# daughtercard.net
KiCad netlist of a schematic drawn in EAGLE
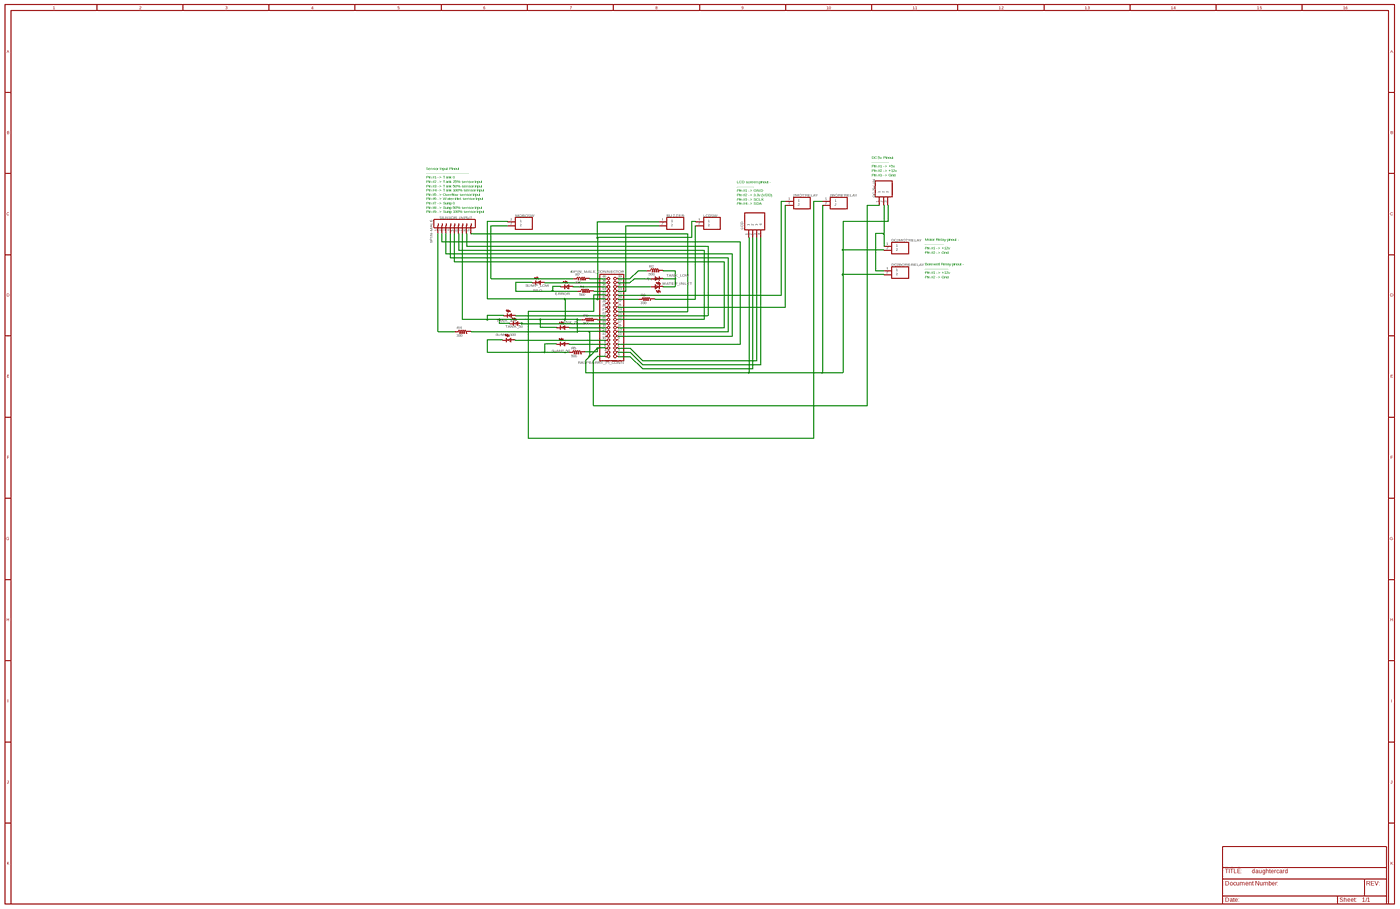
[diagram p0: schematic, sheet 1, overview]
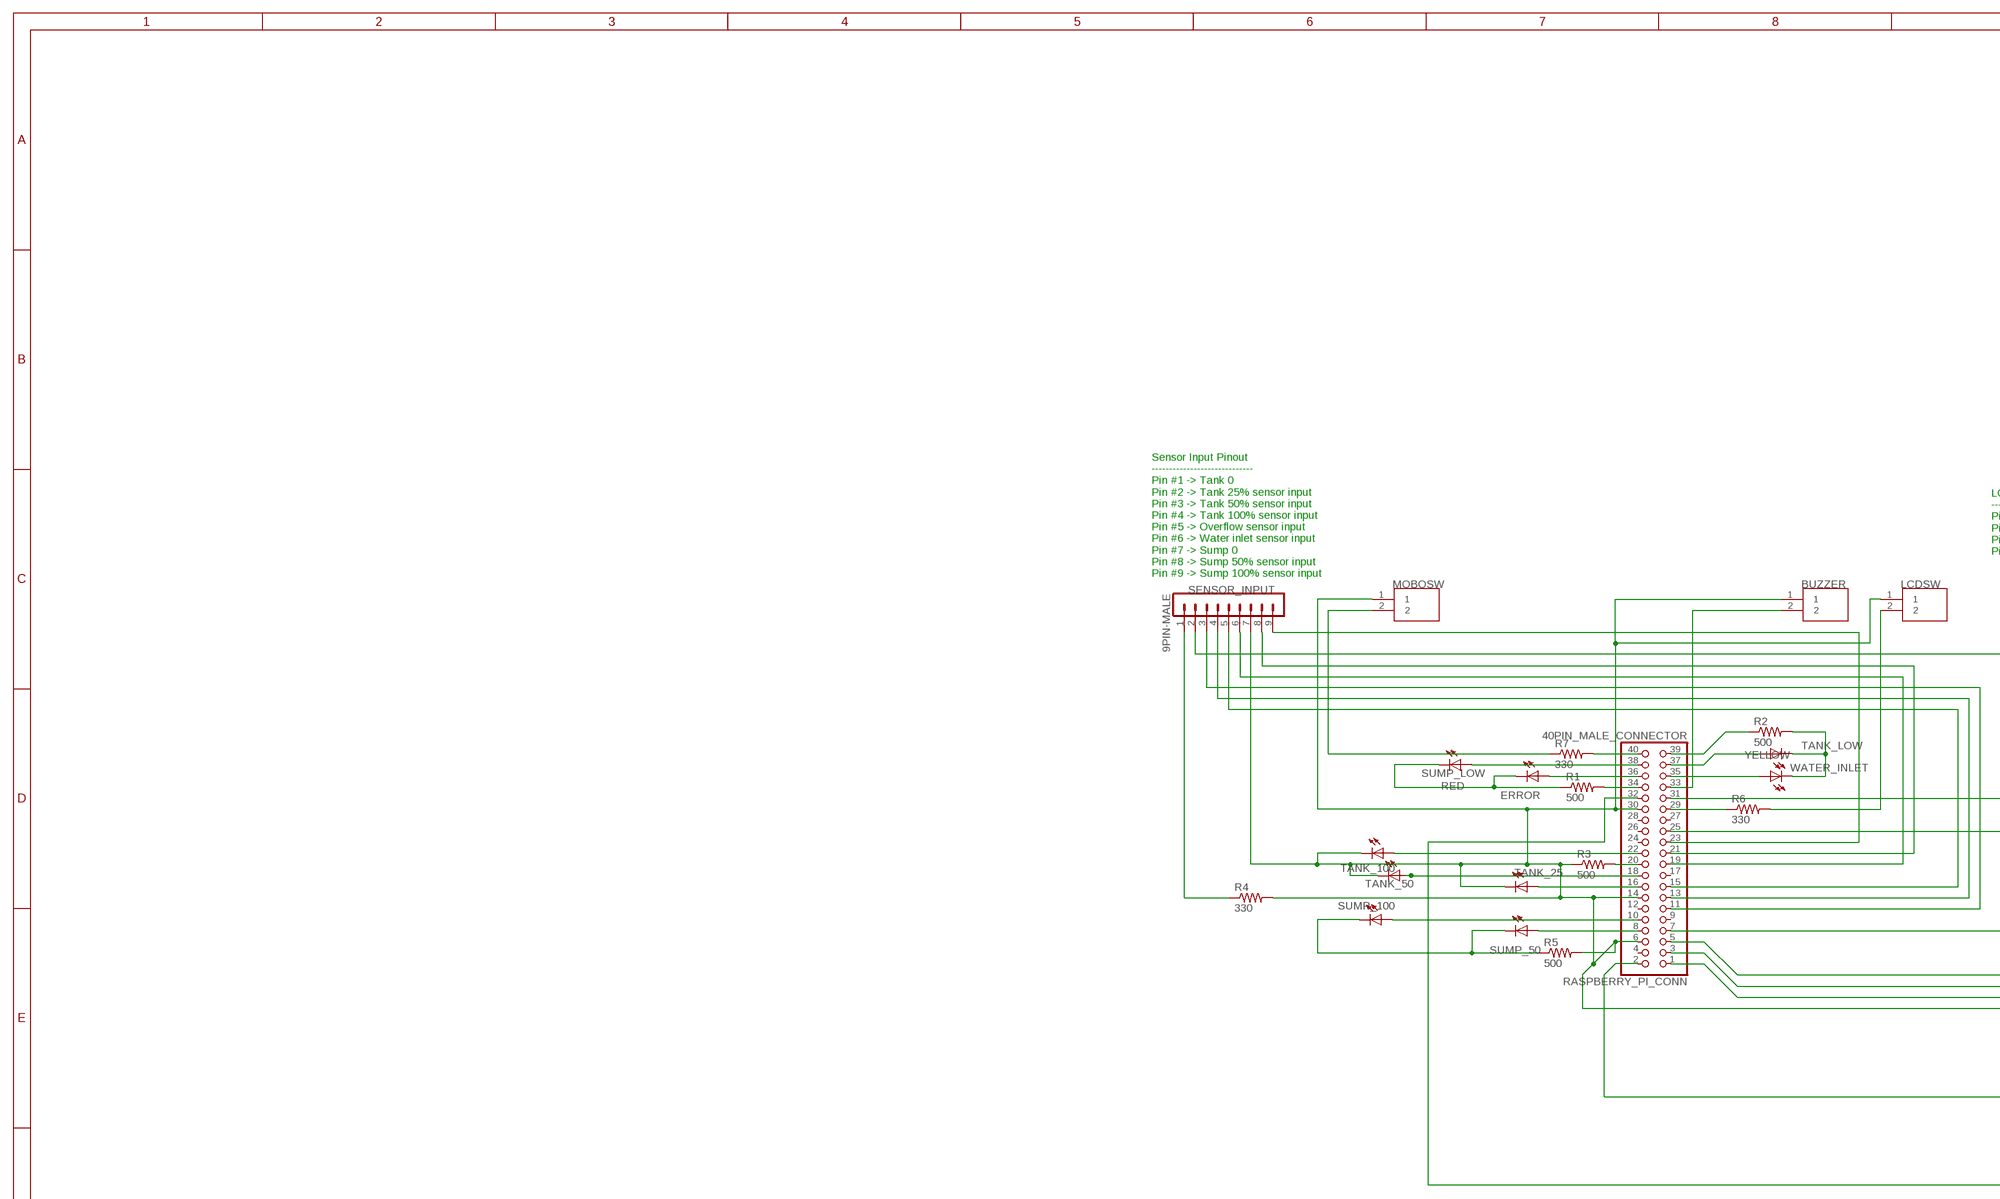
[diagram p1: schematic, sheet 1, part 1 of 4]
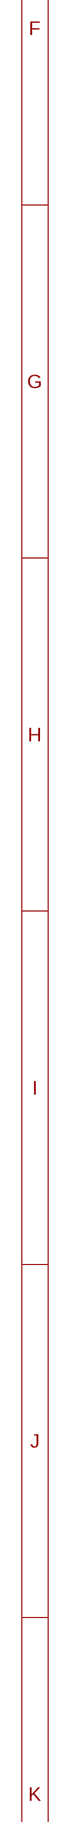
[diagram p2: schematic, sheet 1, part 2 of 4]
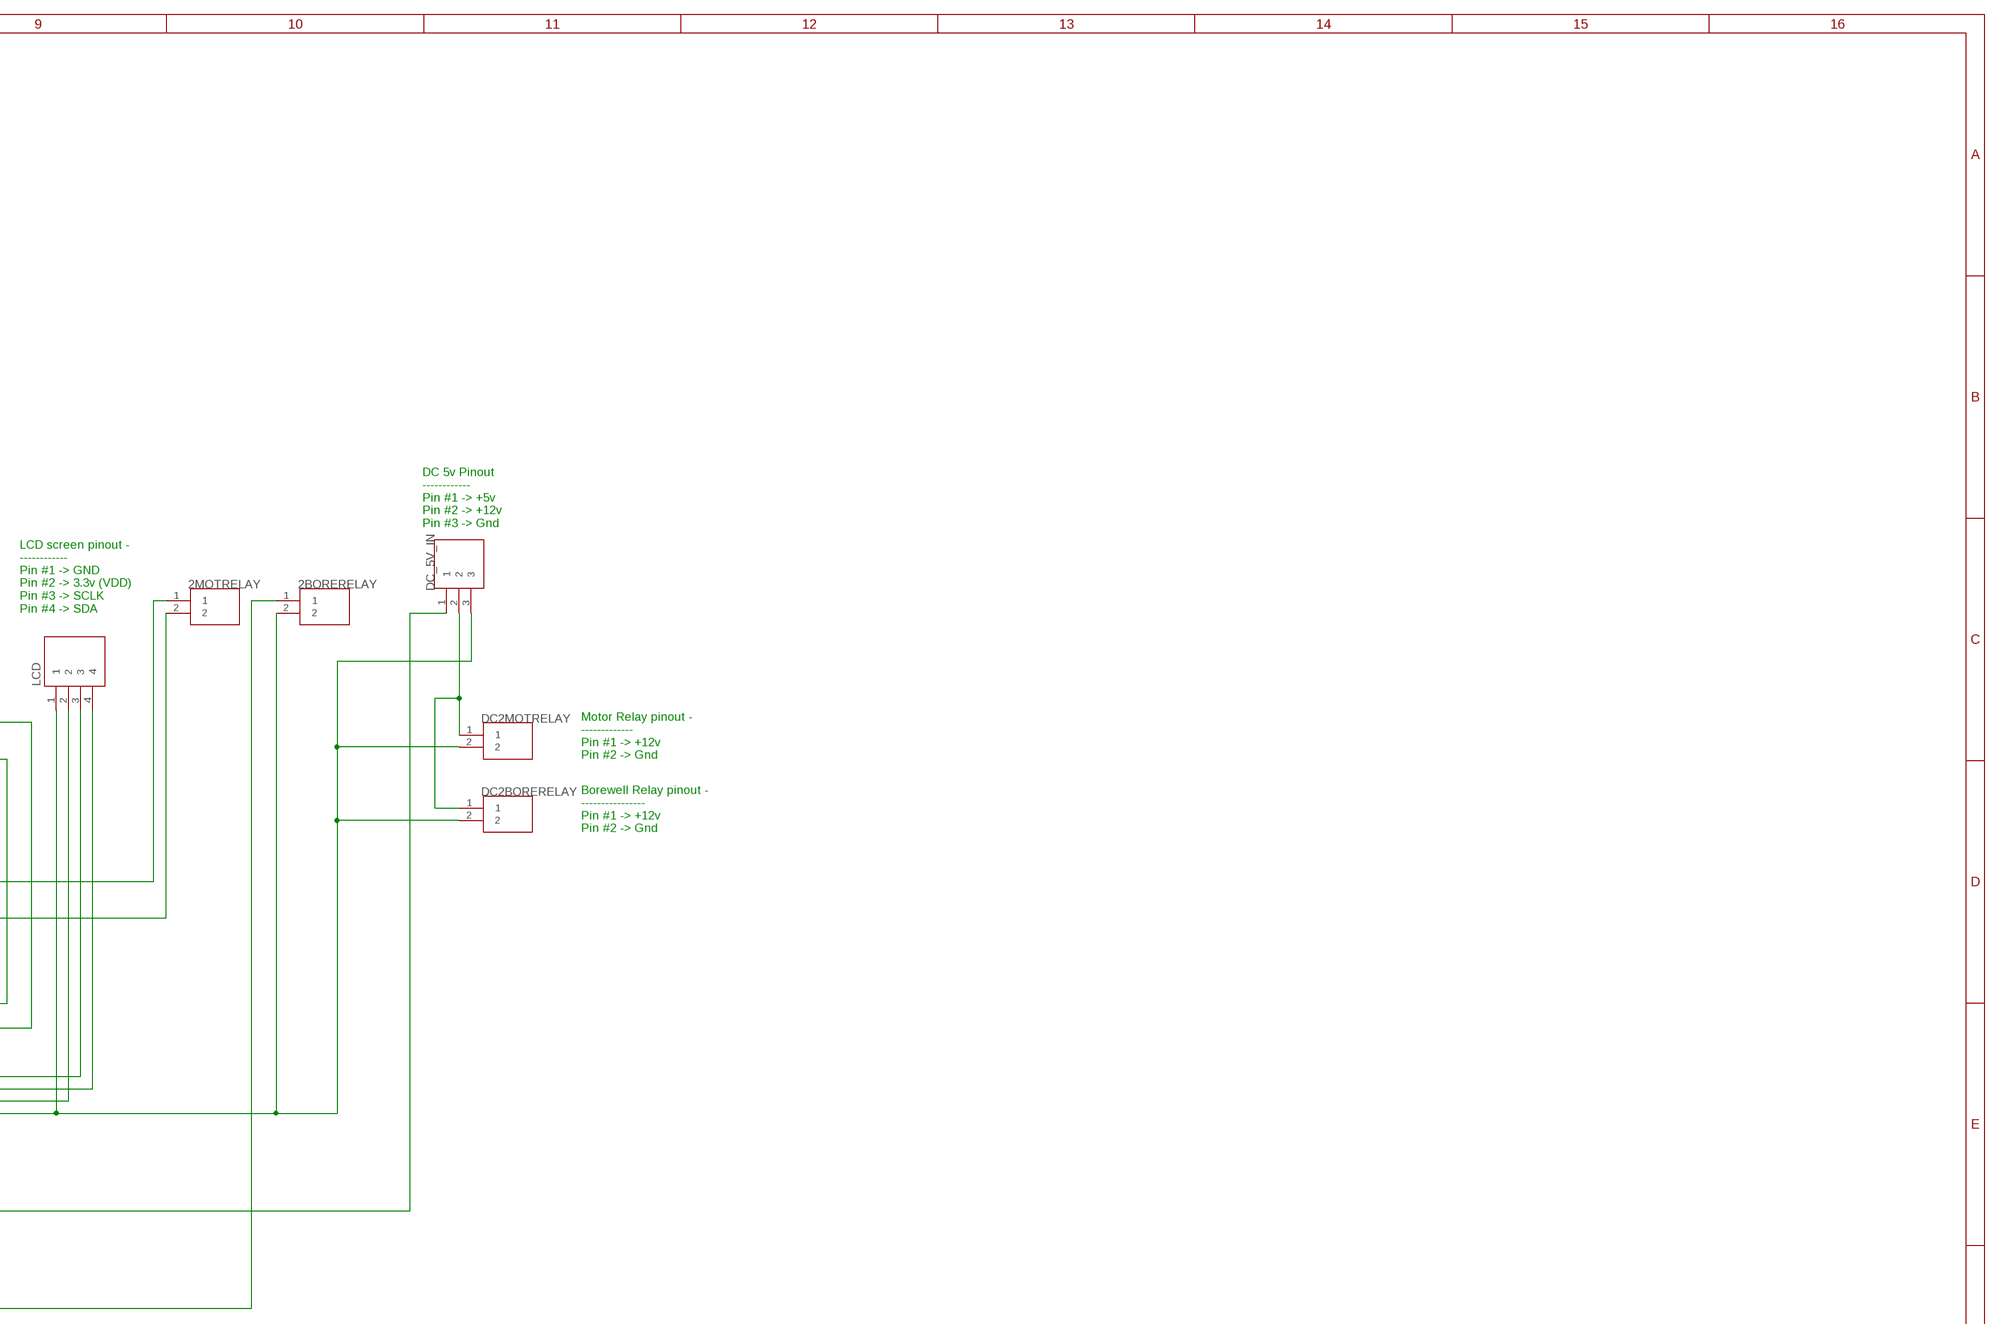
[diagram p3: schematic, sheet 1, part 3 of 4]
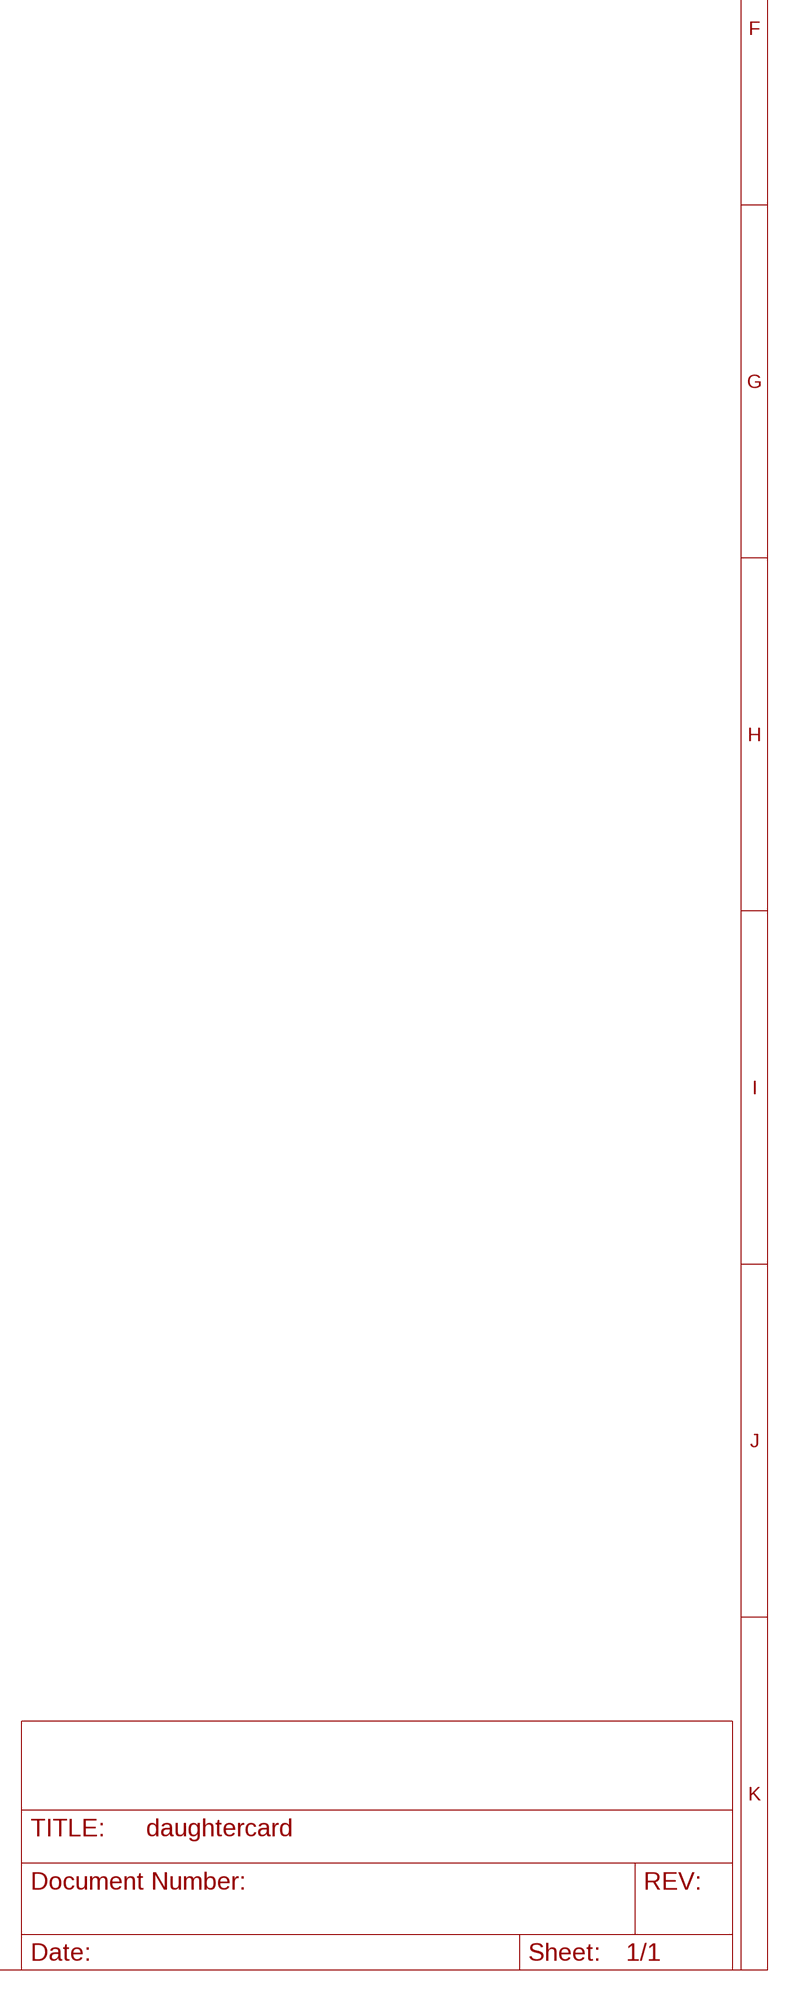
[diagram p4: schematic, sheet 1, part 4 of 4]

(export (version "E")
  (design (tool "Eeschema 10.0.6"))
  (components
    (comp (ref "2BORERELAY")
      (value "440055-2")
      (footprint "eagle-import:TE_440055-2")
      (fields (field (name "MF") "TE Connectivity"))
      (libsource (lib "eagle-import") (part "440055-2"))
    )
    (comp (ref "2MOTRELAY")
      (value "440055-2")
      (footprint "eagle-import:TE_440055-2")
      (fields (field (name "MF") "TE Connectivity"))
      (libsource (lib "eagle-import") (part "440055-2"))
    )
    (comp (ref "BUZZER")
      (value "440055-2")
      (footprint "eagle-import:TE_440055-2")
      (fields (field (name "MF") "TE Connectivity"))
      (libsource (lib "eagle-import") (part "440055-2"))
    )
    (comp (ref "DC2BORERELAY")
      (value "440055-2")
      (footprint "eagle-import:TE_440055-2")
      (fields (field (name "MF") "TE Connectivity"))
      (libsource (lib "eagle-import") (part "440055-2"))
    )
    (comp (ref "DC2MOTRELAY")
      (value "440055-2")
      (footprint "eagle-import:TE_440055-2")
      (fields (field (name "MF") "TE Connectivity"))
      (libsource (lib "eagle-import") (part "440055-2"))
    )
    (comp (ref "DC_5V_IN")
      (value "440052-3")
      (footprint "eagle-import:TE_440052-3")
      (fields (field (name "MF") "TE Connectivity"))
      (libsource (lib "eagle-import") (part "440052-3"))
    )
    (comp (ref "ERROR")
      (value "RED")
      (footprint "eagle-import:LED3MM")
      (libsource (lib "eagle-import") (part "LED3MM"))
    )
    (comp (ref "LCD")
      (value "110990030")
      (footprint "eagle-import:SEEED_110990030")
      (fields (field (name "MF") "Seeed Technology Co., Ltd"))
      (libsource (lib "eagle-import") (part "110990030"))
    )
    (comp (ref "LCDSW")
      (value "440055-2")
      (footprint "eagle-import:TE_440055-2")
      (fields (field (name "MF") "TE Connectivity"))
      (libsource (lib "eagle-import") (part "440055-2"))
    )
    (comp (ref "MOBOSW")
      (value "440055-2")
      (footprint "eagle-import:TE_440055-2")
      (fields (field (name "MF") "TE Connectivity"))
      (libsource (lib "eagle-import") (part "440055-2"))
    )
    (comp (ref "R1")
      (value "500")
      (footprint "eagle-import:0204V")
      (libsource (lib "eagle-import") (part "R-US_0204/2V"))
    )
    (comp (ref "R2")
      (value "500")
      (footprint "eagle-import:0204V")
      (libsource (lib "eagle-import") (part "R-US_0204/2V"))
    )
    (comp (ref "R3")
      (value "500")
      (footprint "eagle-import:0204_7")
      (libsource (lib "eagle-import") (part "R-US_0204/7"))
    )
    (comp (ref "R4")
      (value "330")
      (footprint "eagle-import:0204_7")
      (libsource (lib "eagle-import") (part "R-US_0204/7"))
    )
    (comp (ref "R5")
      (value "500")
      (footprint "eagle-import:0204V")
      (libsource (lib "eagle-import") (part "R-US_0204/2V"))
    )
    (comp (ref "R6")
      (value "330")
      (footprint "eagle-import:0204V")
      (libsource (lib "eagle-import") (part "R-US_0204/2V"))
    )
    (comp (ref "R7")
      (value "330")
      (footprint "eagle-import:0204V")
      (libsource (lib "eagle-import") (part "R-US_0204/2V"))
    )
    (comp (ref "RASPBERRY_PI_CONN")
      (value "40PIN_MALE_CONNECTOR")
      (footprint "eagle-import:2X20")
      (libsource (lib "eagle-import") (part "PINHD-2X20"))
    )
    (comp (ref "SENSOR_INPUT")
      (value "9PIN-MALE")
      (footprint "eagle-import:MA09-1")
      (libsource (lib "eagle-import") (part "MA09-1"))
    )
    (comp (ref "SUMP_50")
      (value "GREEN")
      (footprint "eagle-import:LED3MM")
      (libsource (lib "eagle-import") (part "LED3MM"))
    )
    (comp (ref "SUMP_100")
      (value "GREEN")
      (footprint "eagle-import:LED3MM")
      (libsource (lib "eagle-import") (part "LED3MM"))
    )
    (comp (ref "SUMP_LOW")
      (value "RED")
      (footprint "eagle-import:LED3MM")
      (libsource (lib "eagle-import") (part "LED3MM"))
    )
    (comp (ref "TANK_25")
      (value "GREEN")
      (footprint "eagle-import:LED3MM")
      (libsource (lib "eagle-import") (part "LED3MM"))
    )
    (comp (ref "TANK_50")
      (value "GREEN")
      (footprint "eagle-import:LED3MM")
      (libsource (lib "eagle-import") (part "LED3MM"))
    )
    (comp (ref "TANK_100")
      (value "GREEN")
      (footprint "eagle-import:LED3MM")
      (libsource (lib "eagle-import") (part "LED3MM"))
    )
    (comp (ref "TANK_LOW")
      (value "RED")
      (footprint "eagle-import:LED3MM")
      (libsource (lib "eagle-import") (part "LED3MM"))
    )
    (comp (ref "WATER_INLET")
      (value "YELLOW")
      (footprint "eagle-import:LED3MM")
      (libsource (lib "eagle-import") (part "LED3MM"))
    )
  )
  (nets
    (net (code "1") (name "Net-(2BORERELAY-Pad1)") (class "Default")
      (node (ref "2BORERELAY") (pin "1") (pinfunction "1_1") (pintype "passive"))
      (node (ref "RASPBERRY_PI_CONN") (pin "32") (pinfunction "32_32") (pintype "passive"))
    )
    (net (code "2") (name "Net-(2MOTRELAY-Pad1)") (class "Default")
      (node (ref "2MOTRELAY") (pin "1") (pinfunction "1_1") (pintype "passive"))
      (node (ref "RASPBERRY_PI_CONN") (pin "31") (pinfunction "31_31") (pintype "passive"))
    )
    (net (code "3") (name "Net-(2MOTRELAY-Pad2)") (class "Default")
      (node (ref "2MOTRELAY") (pin "2") (pinfunction "2_2") (pintype "passive"))
      (node (ref "RASPBERRY_PI_CONN") (pin "25") (pinfunction "25_25") (pintype "passive"))
    )
    (net (code "4") (name "Net-(BUZZER-Pad2)") (class "Default")
      (node (ref "BUZZER") (pin "2") (pinfunction "2_2") (pintype "passive"))
      (node (ref "RASPBERRY_PI_CONN") (pin "33") (pinfunction "33_33") (pintype "passive"))
    )
    (net (code "5") (name "Net-(DC2BORERELAY-Pad1)") (class "Default")
      (node (ref "DC2BORERELAY") (pin "1") (pinfunction "1_1") (pintype "passive"))
      (node (ref "DC2MOTRELAY") (pin "1") (pinfunction "1_1") (pintype "passive"))
      (node (ref "DC_5V_IN") (pin "2") (pinfunction "2_2") (pintype "passive"))
    )
    (net (code "6") (name "Net-(DC_5V_IN-Pad1)") (class "Default")
      (node (ref "DC_5V_IN") (pin "1") (pinfunction "1_1") (pintype "passive"))
      (node (ref "RASPBERRY_PI_CONN") (pin "2") (pinfunction "2_2") (pintype "passive"))
    )
    (net (code "7") (name "Net-(ERROR-C)") (class "Default")
      (node (ref "ERROR") (pin "K") (pinfunction "C_K") (pintype "passive"))
      (node (ref "R1") (pin "1") (pinfunction "1_1") (pintype "passive"))
      (node (ref "SUMP_LOW") (pin "K") (pinfunction "C_K") (pintype "passive"))
    )
    (net (code "8") (name "Net-(ERROR-PadA)") (class "Default")
      (node (ref "ERROR") (pin "A") (pinfunction "A_A") (pintype "passive"))
      (node (ref "RASPBERRY_PI_CONN") (pin "36") (pinfunction "36_36") (pintype "passive"))
    )
    (net (code "9") (name "Net-(LCD-Pad2)") (class "Default")
      (node (ref "LCD") (pin "2") (pinfunction "2_2") (pintype "passive"))
      (node (ref "RASPBERRY_PI_CONN") (pin "1") (pinfunction "1_1") (pintype "passive"))
    )
    (net (code "10") (name "Net-(LCD-Pad3)") (class "Default")
      (node (ref "LCD") (pin "3") (pinfunction "3_3") (pintype "passive"))
      (node (ref "RASPBERRY_PI_CONN") (pin "5") (pinfunction "5_5") (pintype "passive"))
    )
    (net (code "11") (name "Net-(LCD-Pad4)") (class "Default")
      (node (ref "LCD") (pin "4") (pinfunction "4_4") (pintype "passive"))
      (node (ref "RASPBERRY_PI_CONN") (pin "3") (pinfunction "3_3") (pintype "passive"))
    )
    (net (code "12") (name "Net-(LCDSW-Pad2)") (class "Default")
      (node (ref "LCDSW") (pin "2") (pinfunction "2_2") (pintype "passive"))
      (node (ref "R6") (pin "2") (pinfunction "2_2") (pintype "passive"))
    )
    (net (code "13") (name "Net-(MOBOSW-Pad2)") (class "Default")
      (node (ref "MOBOSW") (pin "2") (pinfunction "2_2") (pintype "passive"))
      (node (ref "R7") (pin "1") (pinfunction "1_1") (pintype "passive"))
    )
    (net (code "14") (name "Net-(R1-Pad2)") (class "Default")
      (node (ref "R1") (pin "2") (pinfunction "2_2") (pintype "passive"))
      (node (ref "RASPBERRY_PI_CONN") (pin "34") (pinfunction "34_34") (pintype "passive"))
    )
    (net (code "15") (name "Net-(R2-Pad1)") (class "Default")
      (node (ref "R2") (pin "1") (pinfunction "1_1") (pintype "passive"))
      (node (ref "RASPBERRY_PI_CONN") (pin "39") (pinfunction "39_39") (pintype "passive"))
    )
    (net (code "16") (name "Net-(R3-Pad2)") (class "Default")
      (node (ref "R3") (pin "2") (pinfunction "2_2") (pintype "passive"))
      (node (ref "RASPBERRY_PI_CONN") (pin "20") (pinfunction "20_20") (pintype "passive"))
    )
    (net (code "17") (name "Net-(R4-Pad1)") (class "Default")
      (node (ref "R4") (pin "1") (pinfunction "1_1") (pintype "passive"))
      (node (ref "SENSOR_INPUT") (pin "1") (pinfunction "1_1") (pintype "passive"))
    )
    (net (code "18") (name "Net-(R6-Pad1)") (class "Default")
      (node (ref "R6") (pin "1") (pinfunction "1_1") (pintype "passive"))
      (node (ref "RASPBERRY_PI_CONN") (pin "29") (pinfunction "29_29") (pintype "passive"))
    )
    (net (code "19") (name "Net-(R7-Pad2)") (class "Default")
      (node (ref "R7") (pin "2") (pinfunction "2_2") (pintype "passive"))
      (node (ref "RASPBERRY_PI_CONN") (pin "40") (pinfunction "40_40") (pintype "passive"))
    )
    (net (code "20") (name "Net-(RASPBERRY_PI_CONN-Pad7)") (class "Default")
      (node (ref "RASPBERRY_PI_CONN") (pin "7") (pinfunction "7_7") (pintype "passive"))
      (node (ref "SENSOR_INPUT") (pin "2") (pinfunction "2_2") (pintype "passive"))
    )
    (net (code "21") (name "Net-(RASPBERRY_PI_CONN-Pad8)") (class "Default")
      (node (ref "RASPBERRY_PI_CONN") (pin "8") (pinfunction "8_8") (pintype "passive"))
      (node (ref "SUMP_50") (pin "A") (pinfunction "A_A") (pintype "passive"))
    )
    (net (code "22") (name "Net-(RASPBERRY_PI_CONN-Pad10)") (class "Default")
      (node (ref "RASPBERRY_PI_CONN") (pin "10") (pinfunction "10_10") (pintype "passive"))
      (node (ref "SUMP_100") (pin "A") (pinfunction "A_A") (pintype "passive"))
    )
    (net (code "23") (name "Net-(RASPBERRY_PI_CONN-Pad11)") (class "Default")
      (node (ref "RASPBERRY_PI_CONN") (pin "11") (pinfunction "11_11") (pintype "passive"))
      (node (ref "SENSOR_INPUT") (pin "3") (pinfunction "3_3") (pintype "passive"))
    )
    (net (code "24") (name "Net-(RASPBERRY_PI_CONN-Pad13)") (class "Default")
      (node (ref "RASPBERRY_PI_CONN") (pin "13") (pinfunction "13_13") (pintype "passive"))
      (node (ref "SENSOR_INPUT") (pin "4") (pinfunction "4_4") (pintype "passive"))
    )
    (net (code "25") (name "Net-(RASPBERRY_PI_CONN-Pad15)") (class "Default")
      (node (ref "RASPBERRY_PI_CONN") (pin "15") (pinfunction "15_15") (pintype "passive"))
      (node (ref "SENSOR_INPUT") (pin "5") (pinfunction "5_5") (pintype "passive"))
    )
    (net (code "26") (name "Net-(RASPBERRY_PI_CONN-Pad16)") (class "Default")
      (node (ref "RASPBERRY_PI_CONN") (pin "16") (pinfunction "16_16") (pintype "passive"))
      (node (ref "TANK_25") (pin "A") (pinfunction "A_A") (pintype "passive"))
    )
    (net (code "27") (name "Net-(RASPBERRY_PI_CONN-Pad18)") (class "Default")
      (node (ref "RASPBERRY_PI_CONN") (pin "18") (pinfunction "18_18") (pintype "passive"))
      (node (ref "TANK_50") (pin "A") (pinfunction "A_A") (pintype "passive"))
    )
    (net (code "28") (name "Net-(RASPBERRY_PI_CONN-Pad19)") (class "Default")
      (node (ref "RASPBERRY_PI_CONN") (pin "19") (pinfunction "19_19") (pintype "passive"))
      (node (ref "SENSOR_INPUT") (pin "6") (pinfunction "6_6") (pintype "passive"))
    )
    (net (code "29") (name "Net-(RASPBERRY_PI_CONN-Pad21)") (class "Default")
      (node (ref "RASPBERRY_PI_CONN") (pin "21") (pinfunction "21_21") (pintype "passive"))
      (node (ref "SENSOR_INPUT") (pin "8") (pinfunction "8_8") (pintype "passive"))
    )
    (net (code "30") (name "Net-(RASPBERRY_PI_CONN-Pad22)") (class "Default")
      (node (ref "RASPBERRY_PI_CONN") (pin "22") (pinfunction "22_22") (pintype "passive"))
      (node (ref "TANK_100") (pin "A") (pinfunction "A_A") (pintype "passive"))
    )
    (net (code "31") (name "Net-(RASPBERRY_PI_CONN-Pad23)") (class "Default")
      (node (ref "RASPBERRY_PI_CONN") (pin "23") (pinfunction "23_23") (pintype "passive"))
      (node (ref "SENSOR_INPUT") (pin "9") (pinfunction "9_9") (pintype "passive"))
    )
    (net (code "32") (name "Net-(RASPBERRY_PI_CONN-Pad35)") (class "Default")
      (node (ref "RASPBERRY_PI_CONN") (pin "35") (pinfunction "35_35") (pintype "passive"))
      (node (ref "WATER_INLET") (pin "A") (pinfunction "A_A") (pintype "passive"))
    )
    (net (code "33") (name "Net-(RASPBERRY_PI_CONN-Pad37)") (class "Default")
      (node (ref "RASPBERRY_PI_CONN") (pin "37") (pinfunction "37_37") (pintype "passive"))
      (node (ref "TANK_LOW") (pin "A") (pinfunction "A_A") (pintype "passive"))
    )
    (net (code "34") (name "Net-(RASPBERRY_PI_CONN-Pad38)") (class "Default")
      (node (ref "RASPBERRY_PI_CONN") (pin "38") (pinfunction "38_38") (pintype "passive"))
      (node (ref "SUMP_LOW") (pin "A") (pinfunction "A_A") (pintype "passive"))
    )
    (net (code "35") (name "Net-(SUMP_100-C)") (class "Default")
      (node (ref "R5") (pin "1") (pinfunction "1_1") (pintype "passive"))
      (node (ref "SUMP_100") (pin "K") (pinfunction "C_K") (pintype "passive"))
      (node (ref "SUMP_50") (pin "K") (pinfunction "C_K") (pintype "passive"))
    )
    (net (code "36") (name "Net-(TANK_100-C)") (class "Default")
      (node (ref "2BORERELAY") (pin "2") (pinfunction "2_2") (pintype "passive"))
      (node (ref "BUZZER") (pin "1") (pinfunction "1_1") (pintype "passive"))
      (node (ref "DC2BORERELAY") (pin "2") (pinfunction "2_2") (pintype "passive"))
      (node (ref "DC2MOTRELAY") (pin "2") (pinfunction "2_2") (pintype "passive"))
      (node (ref "DC_5V_IN") (pin "3") (pinfunction "3_3") (pintype "passive"))
      (node (ref "LCD") (pin "1") (pinfunction "1_1") (pintype "passive"))
      (node (ref "LCDSW") (pin "1") (pinfunction "1_1") (pintype "passive"))
      (node (ref "MOBOSW") (pin "1") (pinfunction "1_1") (pintype "passive"))
      (node (ref "R3") (pin "1") (pinfunction "1_1") (pintype "passive"))
      (node (ref "R4") (pin "2") (pinfunction "2_2") (pintype "passive"))
      (node (ref "R5") (pin "2") (pinfunction "2_2") (pintype "passive"))
      (node (ref "RASPBERRY_PI_CONN") (pin "14") (pinfunction "14_14") (pintype "passive"))
      (node (ref "RASPBERRY_PI_CONN") (pin "30") (pinfunction "30_30") (pintype "passive"))
      (node (ref "RASPBERRY_PI_CONN") (pin "6") (pinfunction "6_6") (pintype "passive"))
      (node (ref "SENSOR_INPUT") (pin "7") (pinfunction "7_7") (pintype "passive"))
      (node (ref "TANK_100") (pin "K") (pinfunction "C_K") (pintype "passive"))
      (node (ref "TANK_25") (pin "K") (pinfunction "C_K") (pintype "passive"))
      (node (ref "TANK_50") (pin "K") (pinfunction "C_K") (pintype "passive"))
    )
    (net (code "37") (name "Net-(TANK_LOW-C)") (class "Default")
      (node (ref "R2") (pin "2") (pinfunction "2_2") (pintype "passive"))
      (node (ref "TANK_LOW") (pin "K") (pinfunction "C_K") (pintype "passive"))
      (node (ref "WATER_INLET") (pin "K") (pinfunction "C_K") (pintype "passive"))
    )
    (net (code "38") (name "unconnected-(RASPBERRY_PI_CONN-Pad4)") (class "Default")
      (node (ref "RASPBERRY_PI_CONN") (pin "4") (pinfunction "4_4") (pintype "passive"))
    )
    (net (code "39") (name "unconnected-(RASPBERRY_PI_CONN-Pad9)") (class "Default")
      (node (ref "RASPBERRY_PI_CONN") (pin "9") (pinfunction "9_9") (pintype "passive"))
    )
    (net (code "40") (name "unconnected-(RASPBERRY_PI_CONN-Pad12)") (class "Default")
      (node (ref "RASPBERRY_PI_CONN") (pin "12") (pinfunction "12_12") (pintype "passive"))
    )
    (net (code "41") (name "unconnected-(RASPBERRY_PI_CONN-Pad17)") (class "Default")
      (node (ref "RASPBERRY_PI_CONN") (pin "17") (pinfunction "17_17") (pintype "passive"))
    )
    (net (code "42") (name "unconnected-(RASPBERRY_PI_CONN-Pad24)") (class "Default")
      (node (ref "RASPBERRY_PI_CONN") (pin "24") (pinfunction "24_24") (pintype "passive"))
    )
    (net (code "43") (name "unconnected-(RASPBERRY_PI_CONN-Pad26)") (class "Default")
      (node (ref "RASPBERRY_PI_CONN") (pin "26") (pinfunction "26_26") (pintype "passive"))
    )
    (net (code "44") (name "unconnected-(RASPBERRY_PI_CONN-Pad27)") (class "Default")
      (node (ref "RASPBERRY_PI_CONN") (pin "27") (pinfunction "27_27") (pintype "passive"))
    )
    (net (code "45") (name "unconnected-(RASPBERRY_PI_CONN-Pad28)") (class "Default")
      (node (ref "RASPBERRY_PI_CONN") (pin "28") (pinfunction "28_28") (pintype "passive"))
    )
  )
)
